# ADC.net
KiCad netlist of a schematic drawn in Altium Designer
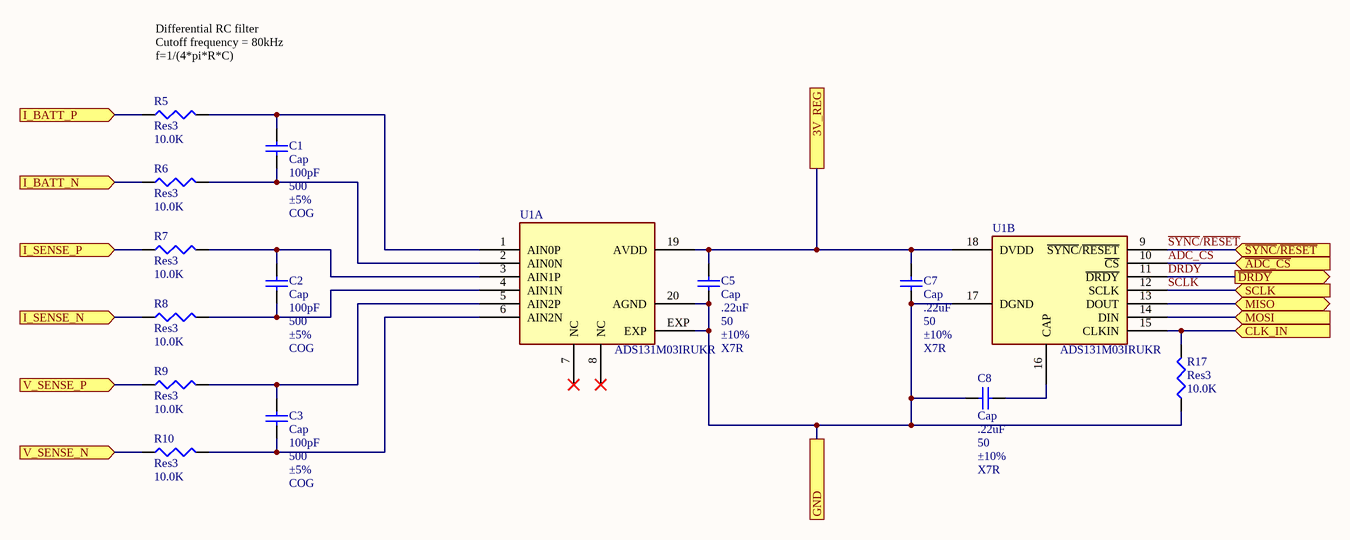
[diagram p0: ADC.SchDoc]

(export (version "E")
  (design (tool "Eeschema 10.0.6"))
  (components
    (comp (ref "C1")
      (value "Cap")
      (footprint "CAPC2012X09M")
      (description "CAP CER 100pF 500v COG 0805")
      (fields
        (field (name "ALTIUM_VALUE") "100pF")
        (field (name "WV") "500")
        (field (name "TOLERANCE") "±5%")
        (field (name "TYPE") "COG")
        (field (name "MPN") "C0805C101JCGACTU")
      )
      (libsource (lib "esd_library") (part "CAP-COG-100pF-500V-±5%"))
    )
    (comp (ref "C2")
      (value "Cap")
      (footprint "CAPC2012X09M")
      (description "CAP CER 100pF 500v COG 0805")
      (fields
        (field (name "ALTIUM_VALUE") "100pF")
        (field (name "WV") "500")
        (field (name "TOLERANCE") "±5%")
        (field (name "TYPE") "COG")
        (field (name "MPN") "C0805C101JCGACTU")
      )
      (libsource (lib "esd_library") (part "CAP-COG-100pF-500V-±5%"))
    )
    (comp (ref "C3")
      (value "Cap")
      (footprint "CAPC2012X09M")
      (description "CAP CER 100pF 500v COG 0805")
      (fields
        (field (name "ALTIUM_VALUE") "100pF")
        (field (name "WV") "500")
        (field (name "TOLERANCE") "±5%")
        (field (name "TYPE") "COG")
        (field (name "MPN") "C0805C101JCGACTU")
      )
      (libsource (lib "esd_library") (part "CAP-COG-100pF-500V-±5%"))
    )
    (comp (ref "C5")
      (value "Cap")
      (footprint "CAPC2012X09M")
      (description "CAP CER .22uF 50v X7R 0805")
      (fields
        (field (name "ALTIUM_VALUE") ".22uF")
        (field (name "WV") "50")
        (field (name "TOLERANCE") "±10%")
        (field (name "TYPE") "X7R")
        (field (name "MPN") "C0805C224K5RACTU")
      )
      (libsource (lib "esd_library") (part "CAP-X7R-.22uF-50V-±10%"))
    )
    (comp (ref "C7")
      (value "Cap")
      (footprint "CAPC2012X09M")
      (description "CAP CER .22uF 50v X7R 0805")
      (fields
        (field (name "ALTIUM_VALUE") ".22uF")
        (field (name "WV") "50")
        (field (name "TOLERANCE") "±10%")
        (field (name "TYPE") "X7R")
        (field (name "MPN") "C0805C224K5RACTU")
      )
      (libsource (lib "esd_library") (part "CAP-X7R-.22uF-50V-±10%"))
    )
    (comp (ref "C8")
      (value "Cap")
      (footprint "CAPC2012X09M")
      (description "CAP CER .22uF 50v X7R 0805")
      (fields
        (field (name "ALTIUM_VALUE") ".22uF")
        (field (name "WV") "50")
        (field (name "TOLERANCE") "±10%")
        (field (name "TYPE") "X7R")
        (field (name "MPN") "C0805C224K5RACTU")
      )
      (libsource (lib "esd_library") (part "CAP-X7R-.22uF-50V-±10%"))
    )
    (comp (ref "R5")
      (value "Res3")
      (footprint "RESC2112X05M")
      (description "RES SMD 10.0K OHM 1% 1/8W 0805")
      (fields (field (name "ALTIUM_VALUE") "10.0K") (field (name "MPN") "CRCW080510K0FKEA"))
      (libsource (lib "esd_library") (part "Resistor_10.0K"))
    )
    (comp (ref "R6")
      (value "Res3")
      (footprint "RESC2112X05M")
      (description "RES SMD 10.0K OHM 1% 1/8W 0805")
      (fields (field (name "ALTIUM_VALUE") "10.0K") (field (name "MPN") "CRCW080510K0FKEA"))
      (libsource (lib "esd_library") (part "Resistor_10.0K"))
    )
    (comp (ref "R7")
      (value "Res3")
      (footprint "RESC2112X05M")
      (description "RES SMD 10.0K OHM 1% 1/8W 0805")
      (fields (field (name "ALTIUM_VALUE") "10.0K") (field (name "MPN") "CRCW080510K0FKEA"))
      (libsource (lib "esd_library") (part "Resistor_10.0K"))
    )
    (comp (ref "R8")
      (value "Res3")
      (footprint "RESC2112X05M")
      (description "RES SMD 10.0K OHM 1% 1/8W 0805")
      (fields (field (name "ALTIUM_VALUE") "10.0K") (field (name "MPN") "CRCW080510K0FKEA"))
      (libsource (lib "esd_library") (part "Resistor_10.0K"))
    )
    (comp (ref "R9")
      (value "Res3")
      (footprint "RESC2112X05M")
      (description "RES SMD 10.0K OHM 1% 1/8W 0805")
      (fields (field (name "ALTIUM_VALUE") "10.0K") (field (name "MPN") "CRCW080510K0FKEA"))
      (libsource (lib "esd_library") (part "Resistor_10.0K"))
    )
    (comp (ref "R10")
      (value "Res3")
      (footprint "RESC2112X05M")
      (description "RES SMD 10.0K OHM 1% 1/8W 0805")
      (fields (field (name "ALTIUM_VALUE") "10.0K") (field (name "MPN") "CRCW080510K0FKEA"))
      (libsource (lib "esd_library") (part "Resistor_10.0K"))
    )
    (comp (ref "R17")
      (value "Res3")
      (footprint "RESC2112X05M")
      (description "RES SMD 10.0K OHM 1% 1/8W 0805")
      (fields (field (name "ALTIUM_VALUE") "10.0K") (field (name "MPN") "CRCW080510K0FKEA"))
      (libsource (lib "esd_library") (part "Resistor_10.0K"))
    )
    (comp (ref "U1")
      (value "ADS131M03IRUKR")
      (footprint "20-WQFN")
      (description "3-Channel, Simultaneously-Sampling, 24-Bit, Delta-Sigma ADC")
      (libsource (lib "ADS131M03IRUKR") (part "ADS131M03IRUKR"))
    )
  )
  (nets
    (net (code "1") (name "/3V_REG") (class "Default")
      (node (ref "C5") (pin "1") (pinfunction "1_1") (pintype "passive"))
      (node (ref "C7") (pin "1") (pinfunction "1_1") (pintype "passive"))
      (node (ref "U1") (pin "18") (pinfunction "DVDD_18") (pintype "passive"))
      (node (ref "U1") (pin "19") (pinfunction "AVDD_19") (pintype "passive"))
    )
    (net (code "2") (name "/CLK_IN") (class "Default")
      (node (ref "R17") (pin "2") (pinfunction "2_2") (pintype "passive"))
      (node (ref "U1") (pin "15") (pinfunction "CLKIN_15") (pintype "passive"))
    )
    (net (code "3") (name "/GND") (class "Default")
      (node (ref "C5") (pin "2") (pinfunction "2_2") (pintype "passive"))
      (node (ref "C7") (pin "2") (pinfunction "2_2") (pintype "passive"))
      (node (ref "C8") (pin "2") (pinfunction "2_2") (pintype "passive"))
      (node (ref "R17") (pin "1") (pinfunction "1_1") (pintype "passive"))
      (node (ref "U1") (pin "17") (pinfunction "DGND_17") (pintype "passive"))
      (node (ref "U1") (pin "20") (pinfunction "AGND_20") (pintype "passive"))
      (node (ref "U1") (pin "EXP") (pinfunction "EXP_EXP") (pintype "passive"))
    )
    (net (code "4") (name "/I_BATT_N") (class "Default")
      (node (ref "R6") (pin "1") (pinfunction "1_1") (pintype "passive"))
    )
    (net (code "5") (name "/I_BATT_P") (class "Default")
      (node (ref "R5") (pin "1") (pinfunction "1_1") (pintype "passive"))
    )
    (net (code "6") (name "/I_SENSE_N") (class "Default")
      (node (ref "R8") (pin "1") (pinfunction "1_1") (pintype "passive"))
    )
    (net (code "7") (name "/I_SENSE_P") (class "Default")
      (node (ref "R7") (pin "1") (pinfunction "1_1") (pintype "passive"))
    )
    (net (code "8") (name "/MISO") (class "Default")
      (node (ref "U1") (pin "13") (pinfunction "DOUT_13") (pintype "passive"))
    )
    (net (code "9") (name "/MOSI") (class "Default")
      (node (ref "U1") (pin "14") (pinfunction "DIN_14") (pintype "passive"))
    )
    (net (code "10") (name "/SCLK") (class "Default")
      (node (ref "U1") (pin "12") (pinfunction "SCLK_12") (pintype "passive"))
    )
    (net (code "11") (name "/V_SENSE_N") (class "Default")
      (node (ref "R10") (pin "1") (pinfunction "1_1") (pintype "passive"))
    )
    (net (code "12") (name "/V_SENSE_P") (class "Default")
      (node (ref "R9") (pin "1") (pinfunction "1_1") (pintype "passive"))
    )
    (net (code "13") (name "/~{ADC_CS}") (class "Default")
      (node (ref "U1") (pin "10") (pinfunction "~{CS}_10") (pintype "passive"))
    )
    (net (code "14") (name "/~{DRDY}") (class "Default")
      (node (ref "U1") (pin "11") (pinfunction "~{DRDY}_11") (pintype "passive"))
    )
    (net (code "15") (name "/~{SYNC}{slash}~{RESET}") (class "Default")
      (node (ref "U1") (pin "9") (pinfunction "~{SYNC}/~{RESET}_9") (pintype "passive"))
    )
    (net (code "16") (name "Net-(U1A-AIN0N)") (class "Default")
      (node (ref "C1") (pin "1") (pinfunction "1_1") (pintype "passive"))
      (node (ref "R6") (pin "2") (pinfunction "2_2") (pintype "passive"))
      (node (ref "U1") (pin "2") (pinfunction "AIN0N_2") (pintype "passive"))
    )
    (net (code "17") (name "Net-(U1A-AIN0P)") (class "Default")
      (node (ref "C1") (pin "2") (pinfunction "2_2") (pintype "passive"))
      (node (ref "R5") (pin "2") (pinfunction "2_2") (pintype "passive"))
      (node (ref "U1") (pin "1") (pinfunction "AIN0P_1") (pintype "passive"))
    )
    (net (code "18") (name "Net-(U1A-AIN1N)") (class "Default")
      (node (ref "C2") (pin "1") (pinfunction "1_1") (pintype "passive"))
      (node (ref "R8") (pin "2") (pinfunction "2_2") (pintype "passive"))
      (node (ref "U1") (pin "4") (pinfunction "AIN1N_4") (pintype "passive"))
    )
    (net (code "19") (name "Net-(U1A-AIN1P)") (class "Default")
      (node (ref "C2") (pin "2") (pinfunction "2_2") (pintype "passive"))
      (node (ref "R7") (pin "2") (pinfunction "2_2") (pintype "passive"))
      (node (ref "U1") (pin "3") (pinfunction "AIN1P_3") (pintype "passive"))
    )
    (net (code "20") (name "Net-(U1A-AIN2N)") (class "Default")
      (node (ref "C3") (pin "1") (pinfunction "1_1") (pintype "passive"))
      (node (ref "R10") (pin "2") (pinfunction "2_2") (pintype "passive"))
      (node (ref "U1") (pin "6") (pinfunction "AIN2N_6") (pintype "passive"))
    )
    (net (code "21") (name "Net-(U1A-AIN2P)") (class "Default")
      (node (ref "C3") (pin "2") (pinfunction "2_2") (pintype "passive"))
      (node (ref "R9") (pin "2") (pinfunction "2_2") (pintype "passive"))
      (node (ref "U1") (pin "5") (pinfunction "AIN2P_5") (pintype "passive"))
    )
    (net (code "22") (name "Net-(U1B-CAP)") (class "Default")
      (node (ref "C8") (pin "1") (pinfunction "1_1") (pintype "passive"))
      (node (ref "U1") (pin "16") (pinfunction "CAP_16") (pintype "passive"))
    )
    (net (code "23") (name "unconnected-(U1A-NC-Pad7)") (class "Default")
      (node (ref "U1") (pin "7") (pinfunction "NC_7") (pintype "passive+no_connect"))
    )
    (net (code "24") (name "unconnected-(U1A-NC-Pad8)") (class "Default")
      (node (ref "U1") (pin "8") (pinfunction "NC_8") (pintype "passive+no_connect"))
    )
  )
)
